# polarization_switch_mid_redo.net
KiCad netlist of a schematic drawn in EAGLE
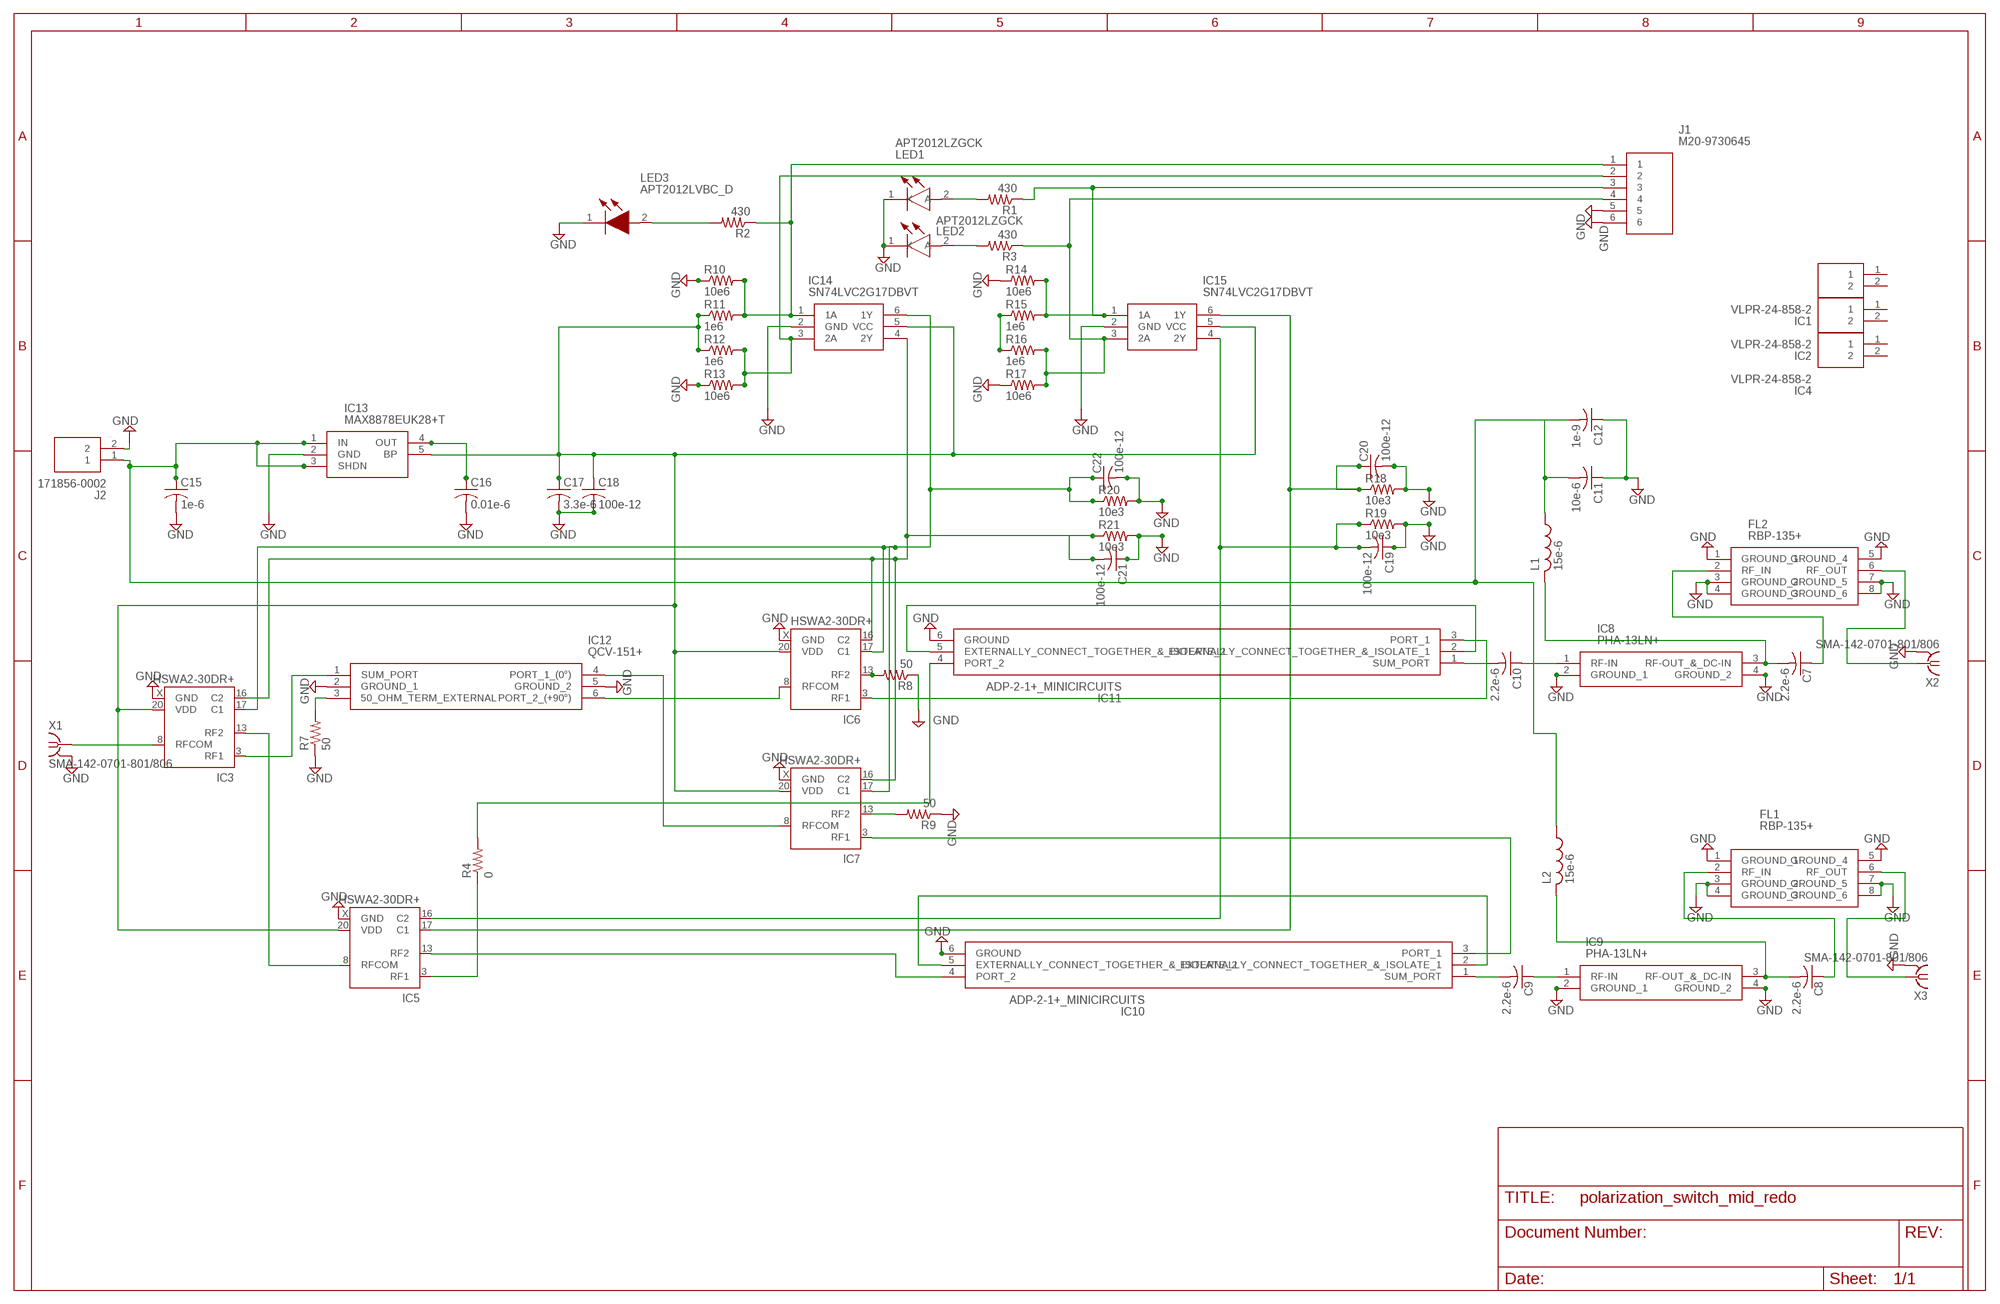
[diagram p0: schematic, sheet 1]

(export (version "E")
  (design (tool "Eeschema 10.0.6"))
  (components
    (comp (ref "C7")
      (value "2.2e-6")
      (footprint "eagle-import:C0603")
      (libsource (lib "eagle-import") (part "C-USC0603"))
    )
    (comp (ref "C8")
      (value "2.2e-6")
      (footprint "eagle-import:C0603")
      (libsource (lib "eagle-import") (part "C-USC0603"))
    )
    (comp (ref "C9")
      (value "2.2e-6")
      (footprint "eagle-import:C0603")
      (libsource (lib "eagle-import") (part "C-USC0603"))
    )
    (comp (ref "C10")
      (value "2.2e-6")
      (footprint "eagle-import:C0603")
      (libsource (lib "eagle-import") (part "C-USC0603"))
    )
    (comp (ref "C11")
      (value "10e-6")
      (footprint "eagle-import:C0603")
      (libsource (lib "eagle-import") (part "C-USC0603"))
    )
    (comp (ref "C12")
      (value "1e-9")
      (footprint "eagle-import:C0603")
      (libsource (lib "eagle-import") (part "C-USC0603"))
    )
    (comp (ref "C15")
      (value "1e-6")
      (footprint "eagle-import:C0603")
      (libsource (lib "eagle-import") (part "C-USC0603"))
    )
    (comp (ref "C16")
      (value "0.01e-6")
      (footprint "eagle-import:C0603")
      (libsource (lib "eagle-import") (part "C-USC0603"))
    )
    (comp (ref "C17")
      (value "3.3e-6")
      (footprint "eagle-import:C0603")
      (libsource (lib "eagle-import") (part "C-USC0603"))
    )
    (comp (ref "C18")
      (value "100e-12")
      (footprint "eagle-import:C0603")
      (libsource (lib "eagle-import") (part "C-USC0603"))
    )
    (comp (ref "C19")
      (value "100e-12")
      (footprint "eagle-import:C0603")
      (libsource (lib "eagle-import") (part "C-USC0603"))
    )
    (comp (ref "C20")
      (value "100e-12")
      (footprint "eagle-import:C0603")
      (libsource (lib "eagle-import") (part "C-USC0603"))
    )
    (comp (ref "C21")
      (value "100e-12")
      (footprint "eagle-import:C0603")
      (libsource (lib "eagle-import") (part "C-USC0603"))
    )
    (comp (ref "C22")
      (value "100e-12")
      (footprint "eagle-import:C0603")
      (libsource (lib "eagle-import") (part "C-USC0603"))
    )
    (comp (ref "FL1")
      (value "RBP-135+")
      (footprint "eagle-import:RBP135")
      (libsource (lib "eagle-import") (part "RBP-135+"))
    )
    (comp (ref "FL2")
      (value "RBP-135+")
      (footprint "eagle-import:RBP135")
      (libsource (lib "eagle-import") (part "RBP-135+"))
    )
    (comp (ref "IC1")
      (value "VLPR-24-858-2")
      (footprint "eagle-import:VLPR248582")
      (fields (field (name "RS_PART_NUMBER") "9063748"))
      (libsource (lib "eagle-import") (part "VLPR-24-858-2"))
    )
    (comp (ref "IC2")
      (value "VLPR-24-858-2")
      (footprint "eagle-import:VLPR248582")
      (fields (field (name "RS_PART_NUMBER") "9063748"))
      (libsource (lib "eagle-import") (part "VLPR-24-858-2"))
    )
    (comp (ref "IC3")
      (value "HSWA2-30DR+")
      (footprint "eagle-import:DG983-1")
      (libsource (lib "eagle-import") (part "HSWA2-30DR+"))
    )
    (comp (ref "IC4")
      (value "VLPR-24-858-2")
      (footprint "eagle-import:VLPR248582")
      (fields (field (name "RS_PART_NUMBER") "9063748"))
      (libsource (lib "eagle-import") (part "VLPR-24-858-2"))
    )
    (comp (ref "IC5")
      (value "HSWA2-30DR+")
      (footprint "eagle-import:DG983-1")
      (libsource (lib "eagle-import") (part "HSWA2-30DR+"))
    )
    (comp (ref "IC6")
      (value "HSWA2-30DR+")
      (footprint "eagle-import:DG983-1")
      (libsource (lib "eagle-import") (part "HSWA2-30DR+"))
    )
    (comp (ref "IC7")
      (value "HSWA2-30DR+")
      (footprint "eagle-import:DG983-1")
      (libsource (lib "eagle-import") (part "HSWA2-30DR+"))
    )
    (comp (ref "IC8")
      (value "PHA-13LN+")
      (footprint "eagle-import:PHA13LN")
      (libsource (lib "eagle-import") (part "PHA-13LN+"))
    )
    (comp (ref "IC9")
      (value "PHA-13LN+")
      (footprint "eagle-import:PHA13LN")
      (libsource (lib "eagle-import") (part "PHA-13LN+"))
    )
    (comp (ref "IC10")
      (value "ADP-2-1+_MINICIRCUITS")
      (footprint "eagle-import:SOTFL254P691X411-6N")
      (fields (field (name "MANUFACTURER_PART_NUMBER") "ADP-2-1+ MINICIRCUITS"))
      (libsource (lib "eagle-import") (part "ADP-2-1+_MINICIRCUITS"))
    )
    (comp (ref "IC11")
      (value "ADP-2-1+_MINICIRCUITS")
      (footprint "eagle-import:SOTFL254P691X411-6N")
      (fields (field (name "MANUFACTURER_PART_NUMBER") "ADP-2-1+ MINICIRCUITS"))
      (libsource (lib "eagle-import") (part "ADP-2-1+_MINICIRCUITS"))
    )
    (comp (ref "IC12")
      (value "QCV-151+")
      (footprint "eagle-import:QCV151")
      (libsource (lib "eagle-import") (part "QCV-151+"))
    )
    (comp (ref "IC13")
      (value "MAX8878EUK28+T")
      (footprint "eagle-import:SOT95P280X145-5N")
      (libsource (lib "eagle-import") (part "MAX8878EUK28+T"))
    )
    (comp (ref "IC14")
      (value "SN74LVC2G17DBVT")
      (footprint "eagle-import:SOT95P280X145-6N")
      (fields
        (field (name "MOUSER_PART_NUMBER") "595-SN74LVC2G17DBVT")
        (field (name "RS_PART_NUMBER") "6628944P")
      )
      (libsource (lib "eagle-import") (part "SN74LVC2G17DBVT"))
    )
    (comp (ref "IC15")
      (value "SN74LVC2G17DBVT")
      (footprint "eagle-import:SOT95P280X145-6N")
      (fields
        (field (name "MOUSER_PART_NUMBER") "595-SN74LVC2G17DBVT")
        (field (name "RS_PART_NUMBER") "6628944P")
      )
      (libsource (lib "eagle-import") (part "SN74LVC2G17DBVT"))
    )
    (comp (ref "J1")
      (value "M20-9730645")
      (footprint "eagle-import:HDRV6W66P0X254_1X6_1524X254X96")
      (fields (field (name "MOUSER_PART_NUMBER") "855-M20-9730645"))
      (libsource (lib "eagle-import") (part "M20-9730645"))
    )
    (comp (ref "J2")
      (value "171856-0002")
      (footprint "eagle-import:SHDR2W90P0X254_1X2_493X635X106")
      (fields
        (field (name "MOUSER_PART_NUMBER") "538-171856-0002")
        (field (name "RS_PART_NUMBER") "7922884P")
      )
      (libsource (lib "eagle-import") (part "171856-0002"))
    )
    (comp (ref "L1")
      (value "15e-6")
      (footprint "eagle-import:L3225M")
      (libsource (lib "eagle-import") (part "L-USL3225M"))
    )
    (comp (ref "L2")
      (value "15e-6")
      (footprint "eagle-import:L3225M")
      (libsource (lib "eagle-import") (part "L-USL3225M"))
    )
    (comp (ref "LED1")
      (value "APT2012LZGCK")
      (footprint "eagle-import:LEDC2012X85N")
      (fields (field (name "MOUSER_PART_NUMBER") "604-APT2012LZGCK"))
      (libsource (lib "eagle-import") (part "APT2012LZGCK"))
    )
    (comp (ref "LED2")
      (value "APT2012LZGCK")
      (footprint "eagle-import:LEDC2012X85N")
      (fields (field (name "MOUSER_PART_NUMBER") "604-APT2012LZGCK"))
      (libsource (lib "eagle-import") (part "APT2012LZGCK"))
    )
    (comp (ref "LED3")
      (value "APT2012LVBC_D")
      (footprint "eagle-import:LEDC2012X85N")
      (fields
        (field (name "ARROW_PART_NUMBER") "APT2012LVBC/D")
        (field (name "MOUSER_PART_NUMBER") "604-APT2012LVBCD")
      )
      (libsource (lib "eagle-import") (part "APT2012LVBC_D"))
    )
    (comp (ref "R1")
      (value "430")
      (footprint "eagle-import:R0603")
      (libsource (lib "eagle-import") (part "R-US_R0603"))
    )
    (comp (ref "R2")
      (value "430")
      (footprint "eagle-import:R0603")
      (libsource (lib "eagle-import") (part "R-US_R0603"))
    )
    (comp (ref "R3")
      (value "430")
      (footprint "eagle-import:R0603")
      (libsource (lib "eagle-import") (part "R-US_R0603"))
    )
    (comp (ref "R4")
      (value "0")
      (footprint "eagle-import:R1206")
      (libsource (lib "eagle-import") (part "R-US_R1206"))
    )
    (comp (ref "R7")
      (value "50")
      (footprint "eagle-import:R0603")
      (libsource (lib "eagle-import") (part "R-US_R0603"))
    )
    (comp (ref "R8")
      (value "50")
      (footprint "eagle-import:R0603")
      (libsource (lib "eagle-import") (part "R-US_R0603"))
    )
    (comp (ref "R9")
      (value "50")
      (footprint "eagle-import:R0603")
      (libsource (lib "eagle-import") (part "R-US_R0603"))
    )
    (comp (ref "R10")
      (value "10e6")
      (footprint "eagle-import:R0603")
      (libsource (lib "eagle-import") (part "R-US_R0603"))
    )
    (comp (ref "R11")
      (value "1e6")
      (footprint "eagle-import:R0603")
      (libsource (lib "eagle-import") (part "R-US_R0603"))
    )
    (comp (ref "R12")
      (value "1e6")
      (footprint "eagle-import:R0603")
      (libsource (lib "eagle-import") (part "R-US_R0603"))
    )
    (comp (ref "R13")
      (value "10e6")
      (footprint "eagle-import:R0603")
      (libsource (lib "eagle-import") (part "R-US_R0603"))
    )
    (comp (ref "R14")
      (value "10e6")
      (footprint "eagle-import:R0603")
      (libsource (lib "eagle-import") (part "R-US_R0603"))
    )
    (comp (ref "R15")
      (value "1e6")
      (footprint "eagle-import:R0603")
      (libsource (lib "eagle-import") (part "R-US_R0603"))
    )
    (comp (ref "R16")
      (value "1e6")
      (footprint "eagle-import:R0603")
      (libsource (lib "eagle-import") (part "R-US_R0603"))
    )
    (comp (ref "R17")
      (value "10e6")
      (footprint "eagle-import:R0603")
      (libsource (lib "eagle-import") (part "R-US_R0603"))
    )
    (comp (ref "R18")
      (value "10e3")
      (footprint "eagle-import:R0603")
      (libsource (lib "eagle-import") (part "R-US_R0603"))
    )
    (comp (ref "R19")
      (value "10e3")
      (footprint "eagle-import:R0603")
      (libsource (lib "eagle-import") (part "R-US_R0603"))
    )
    (comp (ref "R20")
      (value "10e3")
      (footprint "eagle-import:R0603")
      (libsource (lib "eagle-import") (part "R-US_R0603"))
    )
    (comp (ref "R21")
      (value "10e3")
      (footprint "eagle-import:R0603")
      (libsource (lib "eagle-import") (part "R-US_R0603"))
    )
    (comp (ref "X1")
      (value "SMA-142-0701-801/806")
      (footprint "eagle-import:J502-ND-142-0701-801_806")
      (fields (field (name "MF") "JOHNSON COMPONENTS") (field (name "MPN") "142-0701-801"))
      (libsource (lib "eagle-import") (part "SMA-142-0701-801/806"))
    )
    (comp (ref "X2")
      (value "SMA-142-0701-801/806")
      (footprint "eagle-import:J502-ND-142-0701-801_806")
      (fields (field (name "MF") "JOHNSON COMPONENTS") (field (name "MPN") "142-0701-801"))
      (libsource (lib "eagle-import") (part "SMA-142-0701-801/806"))
    )
    (comp (ref "X3")
      (value "SMA-142-0701-801/806")
      (footprint "eagle-import:J502-ND-142-0701-801_806")
      (fields (field (name "MF") "JOHNSON COMPONENTS") (field (name "MPN") "142-0701-801"))
      (libsource (lib "eagle-import") (part "SMA-142-0701-801/806"))
    )
  )
  (nets
    (net (code "1") (name "GND") (class "Default")
      (node (ref "C11") (pin "1") (pinfunction "1_1") (pintype "passive"))
      (node (ref "C12") (pin "1") (pinfunction "1_1") (pintype "passive"))
      (node (ref "C15") (pin "2") (pinfunction "2_2") (pintype "passive"))
      (node (ref "C16") (pin "2") (pinfunction "2_2") (pintype "passive"))
      (node (ref "C17") (pin "2") (pinfunction "2_2") (pintype "passive"))
      (node (ref "C18") (pin "2") (pinfunction "2_2") (pintype "passive"))
      (node (ref "C19") (pin "1") (pinfunction "1_1") (pintype "passive"))
      (node (ref "C20") (pin "2") (pinfunction "2_2") (pintype "passive"))
      (node (ref "C21") (pin "1") (pinfunction "1_1") (pintype "passive"))
      (node (ref "C22") (pin "2") (pinfunction "2_2") (pintype "passive"))
      (node (ref "FL1") (pin "1") (pinfunction "GROUND_1_1") (pintype "bidirectional"))
      (node (ref "FL1") (pin "3") (pinfunction "GROUND_2_3") (pintype "bidirectional"))
      (node (ref "FL1") (pin "4") (pinfunction "GROUND_3_4") (pintype "bidirectional"))
      (node (ref "FL1") (pin "5") (pinfunction "GROUND_4_5") (pintype "bidirectional"))
      (node (ref "FL1") (pin "7") (pinfunction "GROUND_5_7") (pintype "bidirectional"))
      (node (ref "FL1") (pin "8") (pinfunction "GROUND_6_8") (pintype "bidirectional"))
      (node (ref "FL2") (pin "1") (pinfunction "GROUND_1_1") (pintype "bidirectional"))
      (node (ref "FL2") (pin "3") (pinfunction "GROUND_2_3") (pintype "bidirectional"))
      (node (ref "FL2") (pin "4") (pinfunction "GROUND_3_4") (pintype "bidirectional"))
      (node (ref "FL2") (pin "5") (pinfunction "GROUND_4_5") (pintype "bidirectional"))
      (node (ref "FL2") (pin "7") (pinfunction "GROUND_5_7") (pintype "bidirectional"))
      (node (ref "FL2") (pin "8") (pinfunction "GROUND_6_8") (pintype "bidirectional"))
      (node (ref "IC10") (pin "6") (pinfunction "GROUND_6") (pintype "bidirectional"))
      (node (ref "IC11") (pin "6") (pinfunction "GROUND_6") (pintype "bidirectional"))
      (node (ref "IC12") (pin "2") (pinfunction "GROUND_1_2") (pintype "bidirectional"))
      (node (ref "IC12") (pin "5") (pinfunction "GROUND_2_5") (pintype "bidirectional"))
      (node (ref "IC13") (pin "2") (pinfunction "GND_2") (pintype "power_in"))
      (node (ref "IC14") (pin "2") (pinfunction "GND_2") (pintype "bidirectional"))
      (node (ref "IC15") (pin "2") (pinfunction "GND_2") (pintype "bidirectional"))
      (node (ref "IC3") (pin "X") (pinfunction "GND_X") (pintype "power_in"))
      (node (ref "IC5") (pin "X") (pinfunction "GND_X") (pintype "power_in"))
      (node (ref "IC6") (pin "X") (pinfunction "GND_X") (pintype "power_in"))
      (node (ref "IC7") (pin "X") (pinfunction "GND_X") (pintype "power_in"))
      (node (ref "IC8") (pin "2") (pinfunction "GROUND_1_2") (pintype "bidirectional"))
      (node (ref "IC8") (pin "4") (pinfunction "GROUND_2_4") (pintype "bidirectional"))
      (node (ref "IC9") (pin "2") (pinfunction "GROUND_1_2") (pintype "bidirectional"))
      (node (ref "IC9") (pin "4") (pinfunction "GROUND_2_4") (pintype "bidirectional"))
      (node (ref "J1") (pin "5") (pinfunction "5_5") (pintype "bidirectional"))
      (node (ref "J1") (pin "6") (pinfunction "6_6") (pintype "bidirectional"))
      (node (ref "J2") (pin "2") (pinfunction "2_2") (pintype "bidirectional"))
      (node (ref "LED1") (pin "1") (pinfunction "K_1") (pintype "bidirectional"))
      (node (ref "LED2") (pin "1") (pinfunction "K_1") (pintype "bidirectional"))
      (node (ref "LED3") (pin "1") (pinfunction "K_1") (pintype "bidirectional"))
      (node (ref "R10") (pin "1") (pinfunction "1_1") (pintype "passive"))
      (node (ref "R13") (pin "1") (pinfunction "1_1") (pintype "passive"))
      (node (ref "R14") (pin "1") (pinfunction "1_1") (pintype "passive"))
      (node (ref "R17") (pin "1") (pinfunction "1_1") (pintype "passive"))
      (node (ref "R18") (pin "2") (pinfunction "2_2") (pintype "passive"))
      (node (ref "R19") (pin "2") (pinfunction "2_2") (pintype "passive"))
      (node (ref "R20") (pin "2") (pinfunction "2_2") (pintype "passive"))
      (node (ref "R21") (pin "2") (pinfunction "2_2") (pintype "passive"))
      (node (ref "R7") (pin "1") (pinfunction "1_1") (pintype "passive"))
      (node (ref "R8") (pin "1") (pinfunction "1_1") (pintype "passive"))
      (node (ref "R9") (pin "1") (pinfunction "1_1") (pintype "passive"))
      (node (ref "X1") (pin "G@1") (pinfunction "2_G@1") (pintype "passive"))
      (node (ref "X1") (pin "G@2") (pinfunction "2_G@2") (pintype "passive"))
      (node (ref "X1") (pin "G@3") (pinfunction "2_G@3") (pintype "passive"))
      (node (ref "X1") (pin "G@4") (pinfunction "2_G@4") (pintype "passive"))
      (node (ref "X2") (pin "G@1") (pinfunction "2_G@1") (pintype "passive"))
      (node (ref "X2") (pin "G@2") (pinfunction "2_G@2") (pintype "passive"))
      (node (ref "X2") (pin "G@3") (pinfunction "2_G@3") (pintype "passive"))
      (node (ref "X2") (pin "G@4") (pinfunction "2_G@4") (pintype "passive"))
      (node (ref "X3") (pin "G@1") (pinfunction "2_G@1") (pintype "passive"))
      (node (ref "X3") (pin "G@2") (pinfunction "2_G@2") (pintype "passive"))
      (node (ref "X3") (pin "G@3") (pinfunction "2_G@3") (pintype "passive"))
      (node (ref "X3") (pin "G@4") (pinfunction "2_G@4") (pintype "passive"))
    )
    (net (code "2") (name "Net-(FL1-RF_IN)") (class "Default")
      (node (ref "C8") (pin "1") (pinfunction "1_1") (pintype "passive"))
      (node (ref "FL1") (pin "2") (pinfunction "RF_IN_2") (pintype "bidirectional"))
    )
    (net (code "3") (name "Net-(FL1-RF_OUT)") (class "Default")
      (node (ref "FL1") (pin "6") (pinfunction "RF_OUT_6") (pintype "bidirectional"))
      (node (ref "X3") (pin "1") (pinfunction "1_1") (pintype "passive"))
    )
    (net (code "4") (name "Net-(FL2-RF_IN)") (class "Default")
      (node (ref "C7") (pin "1") (pinfunction "1_1") (pintype "passive"))
      (node (ref "FL2") (pin "2") (pinfunction "RF_IN_2") (pintype "bidirectional"))
    )
    (net (code "5") (name "Net-(FL2-RF_OUT)") (class "Default")
      (node (ref "FL2") (pin "6") (pinfunction "RF_OUT_6") (pintype "bidirectional"))
      (node (ref "X2") (pin "1") (pinfunction "1_1") (pintype "passive"))
    )
    (net (code "6") (name "Net-(IC3A-RF2)") (class "Default")
      (node (ref "IC3") (pin "13") (pinfunction "RF2_13") (pintype "passive"))
      (node (ref "IC5") (pin "8") (pinfunction "RFCOM_8") (pintype "passive"))
    )
    (net (code "7") (name "Net-(IC3A-RFCOM)") (class "Default")
      (node (ref "IC3") (pin "8") (pinfunction "RFCOM_8") (pintype "passive"))
      (node (ref "X1") (pin "1") (pinfunction "1_1") (pintype "passive"))
    )
    (net (code "8") (name "Net-(IC5A-RF1)") (class "Default")
      (node (ref "IC5") (pin "3") (pinfunction "RF1_3") (pintype "passive"))
      (node (ref "R4") (pin "1") (pinfunction "1_1") (pintype "passive"))
    )
    (net (code "9") (name "Net-(IC6A-RF2)") (class "Default")
      (node (ref "IC6") (pin "13") (pinfunction "RF2_13") (pintype "passive"))
      (node (ref "R8") (pin "2") (pinfunction "2_2") (pintype "passive"))
    )
    (net (code "10") (name "Net-(IC7A-RF2)") (class "Default")
      (node (ref "IC7") (pin "13") (pinfunction "RF2_13") (pintype "passive"))
      (node (ref "R9") (pin "2") (pinfunction "2_2") (pintype "passive"))
    )
    (net (code "11") (name "Net-(IC8-RF-IN)") (class "Default")
      (node (ref "C10") (pin "1") (pinfunction "1_1") (pintype "passive"))
      (node (ref "IC8") (pin "1") (pinfunction "RF-IN_1") (pintype "bidirectional"))
    )
    (net (code "12") (name "Net-(IC8-RF-OUT_&_DC-IN)") (class "Default")
      (node (ref "C7") (pin "2") (pinfunction "2_2") (pintype "passive"))
      (node (ref "IC8") (pin "3") (pinfunction "RF-OUT_&_DC-IN_3") (pintype "bidirectional"))
      (node (ref "L1") (pin "2") (pinfunction "2_2") (pintype "passive"))
    )
    (net (code "13") (name "Net-(IC9-RF-IN)") (class "Default")
      (node (ref "C9") (pin "1") (pinfunction "1_1") (pintype "passive"))
      (node (ref "IC9") (pin "1") (pinfunction "RF-IN_1") (pintype "bidirectional"))
    )
    (net (code "14") (name "Net-(IC9-RF-OUT_&_DC-IN)") (class "Default")
      (node (ref "C8") (pin "2") (pinfunction "2_2") (pintype "passive"))
      (node (ref "IC9") (pin "3") (pinfunction "RF-OUT_&_DC-IN_3") (pintype "bidirectional"))
      (node (ref "L2") (pin "2") (pinfunction "2_2") (pintype "passive"))
    )
    (net (code "15") (name "Net-(IC10-EXTERNALLY_CONNECT_TOGETHER_&_ISOLATE_1)") (class "Default")
      (node (ref "IC10") (pin "2") (pinfunction "EXTERNALLY_CONNECT_TOGETHER_&_ISOLATE_1_2") (pintype "bidirectional"))
      (node (ref "IC10") (pin "5") (pinfunction "EXTERNALLY_CONNECT_TOGETHER_&_ISOLATE_2_5") (pintype "bidirectional"))
    )
    (net (code "16") (name "Net-(IC10-PORT_1)") (class "Default")
      (node (ref "IC10") (pin "3") (pinfunction "PORT_1_3") (pintype "bidirectional"))
      (node (ref "IC7") (pin "3") (pinfunction "RF1_3") (pintype "passive"))
    )
    (net (code "17") (name "Net-(IC10-PORT_2)") (class "Default")
      (node (ref "IC10") (pin "4") (pinfunction "PORT_2_4") (pintype "bidirectional"))
      (node (ref "IC5") (pin "13") (pinfunction "RF2_13") (pintype "passive"))
    )
    (net (code "18") (name "Net-(IC10-SUM_PORT)") (class "Default")
      (node (ref "C9") (pin "2") (pinfunction "2_2") (pintype "passive"))
      (node (ref "IC10") (pin "1") (pinfunction "SUM_PORT_1") (pintype "bidirectional"))
    )
    (net (code "19") (name "Net-(IC11-EXTERNALLY_CONNECT_TOGETHER_&_ISOLATE_1)") (class "Default")
      (node (ref "IC11") (pin "2") (pinfunction "EXTERNALLY_CONNECT_TOGETHER_&_ISOLATE_1_2") (pintype "bidirectional"))
      (node (ref "IC11") (pin "5") (pinfunction "EXTERNALLY_CONNECT_TOGETHER_&_ISOLATE_2_5") (pintype "bidirectional"))
    )
    (net (code "20") (name "Net-(IC11-PORT_1)") (class "Default")
      (node (ref "IC11") (pin "3") (pinfunction "PORT_1_3") (pintype "bidirectional"))
      (node (ref "IC6") (pin "3") (pinfunction "RF1_3") (pintype "passive"))
    )
    (net (code "21") (name "Net-(IC11-PORT_2)") (class "Default")
      (node (ref "IC11") (pin "4") (pinfunction "PORT_2_4") (pintype "bidirectional"))
      (node (ref "R4") (pin "2") (pinfunction "2_2") (pintype "passive"))
    )
    (net (code "22") (name "Net-(IC11-SUM_PORT)") (class "Default")
      (node (ref "C10") (pin "2") (pinfunction "2_2") (pintype "passive"))
      (node (ref "IC11") (pin "1") (pinfunction "SUM_PORT_1") (pintype "bidirectional"))
    )
    (net (code "23") (name "Net-(IC12-50_OHM_TERM_EXTERNAL)") (class "Default")
      (node (ref "IC12") (pin "3") (pinfunction "50_OHM_TERM_EXTERNAL_3") (pintype "bidirectional"))
      (node (ref "R7") (pin "2") (pinfunction "2_2") (pintype "passive"))
    )
    (net (code "24") (name "Net-(IC12-PORT_1_(0°))") (class "Default")
      (node (ref "IC12") (pin "4") (pinfunction "PORT_1_(0°)_4") (pintype "bidirectional"))
      (node (ref "IC7") (pin "8") (pinfunction "RFCOM_8") (pintype "passive"))
    )
    (net (code "25") (name "Net-(IC12-PORT_2_(+90°))") (class "Default")
      (node (ref "IC12") (pin "6") (pinfunction "PORT_2_(+90°)_6") (pintype "bidirectional"))
      (node (ref "IC6") (pin "8") (pinfunction "RFCOM_8") (pintype "passive"))
    )
    (net (code "26") (name "Net-(IC12-SUM_PORT)") (class "Default")
      (node (ref "IC12") (pin "1") (pinfunction "SUM_PORT_1") (pintype "bidirectional"))
      (node (ref "IC3") (pin "3") (pinfunction "RF1_3") (pintype "passive"))
    )
    (net (code "27") (name "Net-(IC13-BP)") (class "Default")
      (node (ref "C17") (pin "1") (pinfunction "1_1") (pintype "passive"))
      (node (ref "C18") (pin "1") (pinfunction "1_1") (pintype "passive"))
      (node (ref "IC13") (pin "5") (pinfunction "BP_5") (pintype "bidirectional"))
      (node (ref "IC14") (pin "5") (pinfunction "VCC_5") (pintype "bidirectional"))
      (node (ref "IC15") (pin "5") (pinfunction "VCC_5") (pintype "bidirectional"))
      (node (ref "IC3") (pin "20") (pinfunction "VDD_20") (pintype "input"))
      (node (ref "IC5") (pin "20") (pinfunction "VDD_20") (pintype "input"))
      (node (ref "IC6") (pin "20") (pinfunction "VDD_20") (pintype "input"))
      (node (ref "IC7") (pin "20") (pinfunction "VDD_20") (pintype "input"))
      (node (ref "R11") (pin "1") (pinfunction "1_1") (pintype "passive"))
      (node (ref "R12") (pin "1") (pinfunction "1_1") (pintype "passive"))
    )
    (net (code "28") (name "Net-(IC13-IN)") (class "Default")
      (node (ref "C11") (pin "2") (pinfunction "2_2") (pintype "passive"))
      (node (ref "C12") (pin "2") (pinfunction "2_2") (pintype "passive"))
      (node (ref "C15") (pin "1") (pinfunction "1_1") (pintype "passive"))
      (node (ref "IC13") (pin "1") (pinfunction "IN_1") (pintype "input"))
      (node (ref "IC13") (pin "3") (pinfunction "SHDN_3") (pintype "bidirectional"))
      (node (ref "J2") (pin "1") (pinfunction "1_1") (pintype "bidirectional"))
      (node (ref "L1") (pin "1") (pinfunction "1_1") (pintype "passive"))
      (node (ref "L2") (pin "1") (pinfunction "1_1") (pintype "passive"))
    )
    (net (code "29") (name "Net-(IC13-OUT)") (class "Default")
      (node (ref "C16") (pin "1") (pinfunction "1_1") (pintype "passive"))
      (node (ref "IC13") (pin "4") (pinfunction "OUT_4") (pintype "output"))
    )
    (net (code "30") (name "Net-(IC14-1A)") (class "Default")
      (node (ref "IC14") (pin "1") (pinfunction "1A_1") (pintype "bidirectional"))
      (node (ref "J1") (pin "1") (pinfunction "1_1") (pintype "bidirectional"))
      (node (ref "R10") (pin "2") (pinfunction "2_2") (pintype "passive"))
      (node (ref "R11") (pin "2") (pinfunction "2_2") (pintype "passive"))
      (node (ref "R2") (pin "1") (pinfunction "1_1") (pintype "passive"))
    )
    (net (code "31") (name "Net-(IC14-1Y)") (class "Default")
      (node (ref "C22") (pin "1") (pinfunction "1_1") (pintype "passive"))
      (node (ref "IC14") (pin "6") (pinfunction "1Y_6") (pintype "bidirectional"))
      (node (ref "IC3") (pin "17") (pinfunction "C1_17") (pintype "passive"))
      (node (ref "IC6") (pin "17") (pinfunction "C1_17") (pintype "passive"))
      (node (ref "IC7") (pin "17") (pinfunction "C1_17") (pintype "passive"))
      (node (ref "R20") (pin "1") (pinfunction "1_1") (pintype "passive"))
    )
    (net (code "32") (name "Net-(IC14-2A)") (class "Default")
      (node (ref "IC14") (pin "3") (pinfunction "2A_3") (pintype "bidirectional"))
      (node (ref "J1") (pin "2") (pinfunction "2_2") (pintype "bidirectional"))
      (node (ref "R12") (pin "2") (pinfunction "2_2") (pintype "passive"))
      (node (ref "R13") (pin "2") (pinfunction "2_2") (pintype "passive"))
    )
    (net (code "33") (name "Net-(IC14-2Y)") (class "Default")
      (node (ref "C21") (pin "2") (pinfunction "2_2") (pintype "passive"))
      (node (ref "IC14") (pin "4") (pinfunction "2Y_4") (pintype "bidirectional"))
      (node (ref "IC3") (pin "16") (pinfunction "C2_16") (pintype "passive"))
      (node (ref "IC6") (pin "16") (pinfunction "C2_16") (pintype "passive"))
      (node (ref "IC7") (pin "16") (pinfunction "C2_16") (pintype "passive"))
      (node (ref "R21") (pin "1") (pinfunction "1_1") (pintype "passive"))
    )
    (net (code "34") (name "Net-(IC15-1A)") (class "Default")
      (node (ref "IC15") (pin "1") (pinfunction "1A_1") (pintype "bidirectional"))
      (node (ref "J1") (pin "3") (pinfunction "3_3") (pintype "bidirectional"))
      (node (ref "R1") (pin "1") (pinfunction "1_1") (pintype "passive"))
      (node (ref "R14") (pin "2") (pinfunction "2_2") (pintype "passive"))
      (node (ref "R15") (pin "2") (pinfunction "2_2") (pintype "passive"))
    )
    (net (code "35") (name "Net-(IC15-1Y)") (class "Default")
      (node (ref "C20") (pin "1") (pinfunction "1_1") (pintype "passive"))
      (node (ref "IC15") (pin "6") (pinfunction "1Y_6") (pintype "bidirectional"))
      (node (ref "IC5") (pin "17") (pinfunction "C1_17") (pintype "passive"))
      (node (ref "R18") (pin "1") (pinfunction "1_1") (pintype "passive"))
    )
    (net (code "36") (name "Net-(IC15-2A)") (class "Default")
      (node (ref "IC15") (pin "3") (pinfunction "2A_3") (pintype "bidirectional"))
      (node (ref "J1") (pin "4") (pinfunction "4_4") (pintype "bidirectional"))
      (node (ref "R16") (pin "2") (pinfunction "2_2") (pintype "passive"))
      (node (ref "R17") (pin "2") (pinfunction "2_2") (pintype "passive"))
      (node (ref "R3") (pin "1") (pinfunction "1_1") (pintype "passive"))
    )
    (net (code "37") (name "Net-(IC15-2Y)") (class "Default")
      (node (ref "C19") (pin "2") (pinfunction "2_2") (pintype "passive"))
      (node (ref "IC15") (pin "4") (pinfunction "2Y_4") (pintype "bidirectional"))
      (node (ref "IC5") (pin "16") (pinfunction "C2_16") (pintype "passive"))
      (node (ref "R19") (pin "1") (pinfunction "1_1") (pintype "passive"))
    )
    (net (code "38") (name "Net-(LED1-A)") (class "Default")
      (node (ref "LED1") (pin "2") (pinfunction "A_2") (pintype "bidirectional"))
      (node (ref "R1") (pin "2") (pinfunction "2_2") (pintype "passive"))
    )
    (net (code "39") (name "Net-(LED2-A)") (class "Default")
      (node (ref "LED2") (pin "2") (pinfunction "A_2") (pintype "bidirectional"))
      (node (ref "R3") (pin "2") (pinfunction "2_2") (pintype "passive"))
    )
    (net (code "40") (name "Net-(LED3-A)") (class "Default")
      (node (ref "LED3") (pin "2") (pinfunction "A_2") (pintype "bidirectional"))
      (node (ref "R2") (pin "2") (pinfunction "2_2") (pintype "passive"))
    )
    (net (code "41") (name "Net-(R15-Pad1)") (class "Default")
      (node (ref "R15") (pin "1") (pinfunction "1_1") (pintype "passive"))
      (node (ref "R16") (pin "1") (pinfunction "1_1") (pintype "passive"))
    )
    (net (code "42") (name "unconnected-(IC1-Pad1)") (class "Default")
      (node (ref "IC1") (pin "1") (pinfunction "1_1") (pintype "bidirectional"))
    )
    (net (code "43") (name "unconnected-(IC1-Pad2)") (class "Default")
      (node (ref "IC1") (pin "2") (pinfunction "2_2") (pintype "bidirectional"))
    )
    (net (code "44") (name "unconnected-(IC2-Pad1)") (class "Default")
      (node (ref "IC2") (pin "1") (pinfunction "1_1") (pintype "bidirectional"))
    )
    (net (code "45") (name "unconnected-(IC2-Pad2)") (class "Default")
      (node (ref "IC2") (pin "2") (pinfunction "2_2") (pintype "bidirectional"))
    )
    (net (code "46") (name "unconnected-(IC4-Pad1)") (class "Default")
      (node (ref "IC4") (pin "1") (pinfunction "1_1") (pintype "bidirectional"))
    )
    (net (code "47") (name "unconnected-(IC4-Pad2)") (class "Default")
      (node (ref "IC4") (pin "2") (pinfunction "2_2") (pintype "bidirectional"))
    )
  )
)
